# magbead_v4.net
KiCad netlist of a schematic drawn in EAGLE
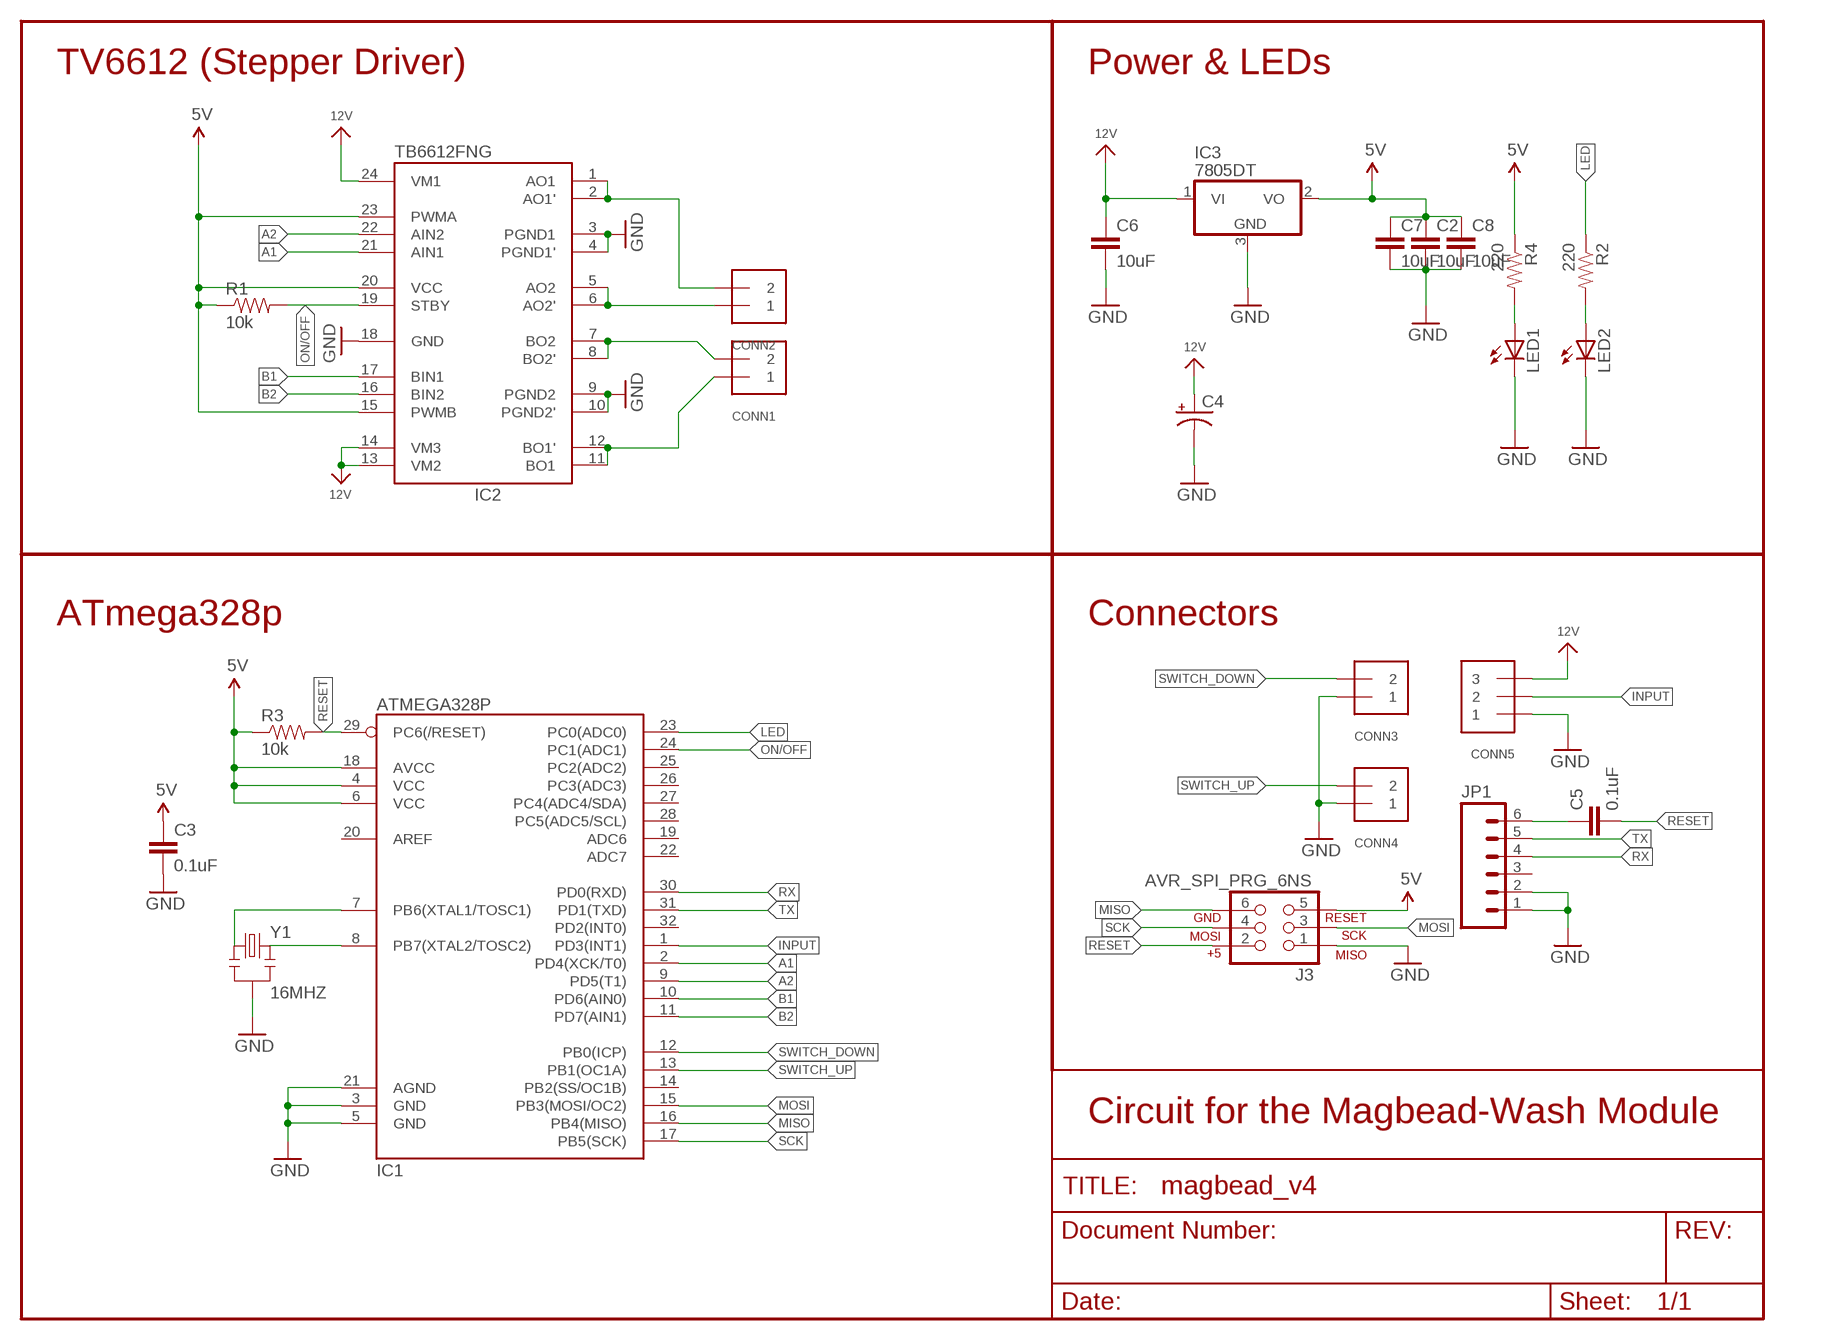
[diagram p0: schematic, sheet 1]

(export (version "E")
  (design (tool "Eeschema 10.0.6"))
  (components
    (comp (ref "C2")
      (value "10uF")
      (footprint "eagle-import:0805")
      (libsource (lib "eagle-import") (part "CAP0805"))
    )
    (comp (ref "C3")
      (value "0.1uF")
      (footprint "eagle-import:0603-CAP")
      (libsource (lib "eagle-import") (part "CAP0603-CAP"))
    )
    (comp (ref "C4")
      (value "CAP_POLD")
      (footprint "eagle-import:PANASONIC_D")
      (libsource (lib "eagle-import") (part "CAP_POLD"))
    )
    (comp (ref "C5")
      (value "0.1uF")
      (footprint "eagle-import:0603-CAP")
      (libsource (lib "eagle-import") (part "CAP0603-CAP"))
    )
    (comp (ref "C6")
      (value "10uF")
      (footprint "eagle-import:0805")
      (libsource (lib "eagle-import") (part "CAP0805"))
    )
    (comp (ref "C7")
      (value "10uF")
      (footprint "eagle-import:0805")
      (libsource (lib "eagle-import") (part "CAP0805"))
    )
    (comp (ref "C8")
      (value "10uF")
      (footprint "eagle-import:0805")
      (libsource (lib "eagle-import") (part "CAP0805"))
    )
    (comp (ref "CONN1")
      (value "TERMBLOCK_1X2")
      (footprint "eagle-import:TERMBLOCK_1X2-3.5MM")
      (libsource (lib "eagle-import") (part "TERMBLOCK_1X2"))
    )
    (comp (ref "CONN2")
      (value "TERMBLOCK_1X2")
      (footprint "eagle-import:TERMBLOCK_1X2-3.5MM")
      (libsource (lib "eagle-import") (part "TERMBLOCK_1X2"))
    )
    (comp (ref "CONN3")
      (value "TERMBLOCK_1X2")
      (footprint "eagle-import:TERMBLOCK_1X2-3.5MM")
      (libsource (lib "eagle-import") (part "TERMBLOCK_1X2"))
    )
    (comp (ref "CONN4")
      (value "TERMBLOCK_1X2")
      (footprint "eagle-import:TERMBLOCK_1X2-3.5MM")
      (libsource (lib "eagle-import") (part "TERMBLOCK_1X2"))
    )
    (comp (ref "CONN5")
      (value "TERMBLOCK_1X3")
      (footprint "eagle-import:TERMBLOCK_1X3-3.5MM")
      (libsource (lib "eagle-import") (part "TERMBLOCK_1X3"))
    )
    (comp (ref "IC1")
      (value "ATMEGA328P")
      (footprint "eagle-import:TQFP32-08")
      (libsource (lib "eagle-import") (part "ATMEGA328_SMT"))
    )
    (comp (ref "IC2")
      (value "TB6612FNG")
      (footprint "eagle-import:SSOP24")
      (libsource (lib "eagle-import") (part "TB6612FNG"))
    )
    (comp (ref "IC3")
      (value "7805DT")
      (footprint "eagle-import:TO252")
      (libsource (lib "eagle-import") (part "78DT05"))
    )
    (comp (ref "J3")
      (value "AVR_SPI_PRG_6NS")
      (footprint "eagle-import:2X3-NS")
      (libsource (lib "eagle-import") (part "AVR_SPI_PRG_6NS"))
    )
    (comp (ref "JP1")
      (value "M06SIP")
      (footprint "eagle-import:1X06")
      (libsource (lib "eagle-import") (part "M06SIP"))
    )
    (comp (ref "LED1")
      (value "LEDCHIP-LED0603")
      (footprint "eagle-import:CHIP-LED0603")
      (libsource (lib "eagle-import") (part "LEDCHIP-LED0603"))
    )
    (comp (ref "LED2")
      (value "LEDCHIP-LED0603")
      (footprint "eagle-import:CHIP-LED0603")
      (libsource (lib "eagle-import") (part "LEDCHIP-LED0603"))
    )
    (comp (ref "R1")
      (value "10k")
      (footprint "eagle-import:0603-RES")
      (libsource (lib "eagle-import") (part "RESISTOR0603-RES"))
    )
    (comp (ref "R2")
      (value "220")
      (footprint "eagle-import:0603-RES")
      (libsource (lib "eagle-import") (part "RESISTOR0603-RES"))
    )
    (comp (ref "R3")
      (value "10k")
      (footprint "eagle-import:0603-RES")
      (libsource (lib "eagle-import") (part "RESISTOR0603-RES"))
    )
    (comp (ref "R4")
      (value "220")
      (footprint "eagle-import:0603-RES")
      (libsource (lib "eagle-import") (part "RESISTOR0603-RES"))
    )
    (comp (ref "Y1")
      (value "16MHZ")
      (footprint "eagle-import:RESONATOR-SMD")
      (libsource (lib "eagle-import") (part "RESONATOR16MHZ"))
    )
  )
  (nets
    (net (code "1") (name "5V") (class "Default")
      (node (ref "C2") (pin "1") (pinfunction "1_1") (pintype "passive"))
      (node (ref "C3") (pin "1") (pinfunction "1_1") (pintype "passive"))
      (node (ref "C7") (pin "1") (pinfunction "1_1") (pintype "passive"))
      (node (ref "C8") (pin "1") (pinfunction "1_1") (pintype "passive"))
      (node (ref "IC1") (pin "18") (pinfunction "AVCC_18") (pintype "bidirectional"))
      (node (ref "IC1") (pin "4") (pinfunction "VCC_4") (pintype "bidirectional"))
      (node (ref "IC1") (pin "6") (pinfunction "VCC_6") (pintype "bidirectional"))
      (node (ref "IC2") (pin "15") (pinfunction "PWMB_15") (pintype "input"))
      (node (ref "IC2") (pin "20") (pinfunction "VCC_20") (pintype "power_in"))
      (node (ref "IC2") (pin "23") (pinfunction "PWMA_23") (pintype "input"))
      (node (ref "IC3") (pin "2") (pinfunction "VO_2") (pintype "passive"))
      (node (ref "J3") (pin "5") (pinfunction "5_5") (pintype "passive"))
      (node (ref "R1") (pin "1") (pinfunction "1_1") (pintype "passive"))
      (node (ref "R3") (pin "1") (pinfunction "1_1") (pintype "passive"))
      (node (ref "R4") (pin "1") (pinfunction "1_1") (pintype "passive"))
    )
    (net (code "2") (name "12V") (class "Default")
      (node (ref "C4") (pin "+") (pinfunction "+_+") (pintype "passive"))
      (node (ref "C6") (pin "1") (pinfunction "1_1") (pintype "passive"))
      (node (ref "CONN5") (pin "3") (pinfunction "3_3") (pintype "passive"))
      (node (ref "IC2") (pin "13") (pinfunction "VM2_13") (pintype "power_in"))
      (node (ref "IC2") (pin "14") (pinfunction "VM3_14") (pintype "power_in"))
      (node (ref "IC2") (pin "24") (pinfunction "VM1_24") (pintype "power_in"))
      (node (ref "IC3") (pin "1") (pinfunction "VI_1") (pintype "input"))
    )
    (net (code "3") (name "A1") (class "Default")
      (node (ref "IC1") (pin "2") (pinfunction "PD4(XCK/T0)_2") (pintype "bidirectional"))
      (node (ref "IC2") (pin "21") (pinfunction "AIN1_21") (pintype "input"))
    )
    (net (code "4") (name "A2") (class "Default")
      (node (ref "IC1") (pin "9") (pinfunction "PD5(T1)_9") (pintype "bidirectional"))
      (node (ref "IC2") (pin "22") (pinfunction "AIN2_22") (pintype "input"))
    )
    (net (code "5") (name "B1") (class "Default")
      (node (ref "IC1") (pin "10") (pinfunction "PD6(AIN0)_10") (pintype "bidirectional"))
      (node (ref "IC2") (pin "17") (pinfunction "BIN1_17") (pintype "input"))
    )
    (net (code "6") (name "B2") (class "Default")
      (node (ref "IC1") (pin "11") (pinfunction "PD7(AIN1)_11") (pintype "bidirectional"))
      (node (ref "IC2") (pin "16") (pinfunction "BIN2_16") (pintype "input"))
    )
    (net (code "7") (name "GND") (class "Default")
      (node (ref "C2") (pin "2") (pinfunction "2_2") (pintype "passive"))
      (node (ref "C3") (pin "2") (pinfunction "2_2") (pintype "passive"))
      (node (ref "C4") (pin "-") (pinfunction "-_-") (pintype "passive"))
      (node (ref "C6") (pin "2") (pinfunction "2_2") (pintype "passive"))
      (node (ref "C7") (pin "2") (pinfunction "2_2") (pintype "passive"))
      (node (ref "C8") (pin "2") (pinfunction "2_2") (pintype "passive"))
      (node (ref "CONN3") (pin "1") (pinfunction "1_1") (pintype "passive"))
      (node (ref "CONN4") (pin "1") (pinfunction "1_1") (pintype "passive"))
      (node (ref "CONN5") (pin "1") (pinfunction "1_1") (pintype "passive"))
      (node (ref "IC1") (pin "21") (pinfunction "AGND_21") (pintype "bidirectional"))
      (node (ref "IC1") (pin "3") (pinfunction "GND_3") (pintype "bidirectional"))
      (node (ref "IC1") (pin "5") (pinfunction "GND_5") (pintype "bidirectional"))
      (node (ref "IC2") (pin "10") (pinfunction "PGND2'_10") (pintype "power_in"))
      (node (ref "IC2") (pin "18") (pinfunction "GND_18") (pintype "power_in"))
      (node (ref "IC2") (pin "3") (pinfunction "PGND1_3") (pintype "power_in"))
      (node (ref "IC2") (pin "4") (pinfunction "PGND1'_4") (pintype "power_in"))
      (node (ref "IC2") (pin "9") (pinfunction "PGND2_9") (pintype "power_in"))
      (node (ref "IC3") (pin "3") (pinfunction "GND_3") (pintype "passive"))
      (node (ref "J3") (pin "1") (pinfunction "1_1") (pintype "passive"))
      (node (ref "JP1") (pin "1") (pinfunction "1_1") (pintype "passive"))
      (node (ref "JP1") (pin "2") (pinfunction "2_2") (pintype "passive"))
      (node (ref "LED1") (pin "C") (pinfunction "C_C") (pintype "passive"))
      (node (ref "LED2") (pin "C") (pinfunction "C_C") (pintype "passive"))
      (node (ref "Y1") (pin "2") (pinfunction "2_2") (pintype "passive"))
    )
    (net (code "8") (name "INPUT") (class "Default")
      (node (ref "CONN5") (pin "2") (pinfunction "2_2") (pintype "passive"))
      (node (ref "IC1") (pin "1") (pinfunction "PD3(INT1)_1") (pintype "bidirectional"))
    )
    (net (code "9") (name "LED") (class "Default")
      (node (ref "IC1") (pin "23") (pinfunction "PC0(ADC0)_23") (pintype "bidirectional"))
      (node (ref "R2") (pin "1") (pinfunction "1_1") (pintype "passive"))
    )
    (net (code "10") (name "MISO") (class "Default")
      (node (ref "IC1") (pin "16") (pinfunction "PB4(MISO)_16") (pintype "bidirectional"))
      (node (ref "J3") (pin "6") (pinfunction "6_6") (pintype "passive"))
    )
    (net (code "11") (name "MOSI") (class "Default")
      (node (ref "IC1") (pin "15") (pinfunction "PB3(MOSI/OC2)_15") (pintype "bidirectional"))
      (node (ref "J3") (pin "3") (pinfunction "3_3") (pintype "passive"))
    )
    (net (code "12") (name "Net-(C5-Pad1)") (class "Default")
      (node (ref "C5") (pin "1") (pinfunction "1_1") (pintype "passive"))
      (node (ref "JP1") (pin "6") (pinfunction "6_6") (pintype "passive"))
    )
    (net (code "13") (name "Net-(IC1-PB6(XTAL1{slash}TOSC1))") (class "Default")
      (node (ref "IC1") (pin "7") (pinfunction "PB6(XTAL1/TOSC1)_7") (pintype "bidirectional"))
      (node (ref "Y1") (pin "1") (pinfunction "1_1") (pintype "passive"))
    )
    (net (code "14") (name "Net-(IC1-PB7(XTAL2{slash}TOSC2))") (class "Default")
      (node (ref "IC1") (pin "8") (pinfunction "PB7(XTAL2/TOSC2)_8") (pintype "bidirectional"))
      (node (ref "Y1") (pin "3") (pinfunction "3_3") (pintype "passive"))
    )
    (net (code "15") (name "Net-(IC2-AO1')") (class "Default")
      (node (ref "CONN2") (pin "2") (pinfunction "2_2") (pintype "passive"))
      (node (ref "IC2") (pin "1") (pinfunction "AO1_1") (pintype "output"))
      (node (ref "IC2") (pin "2") (pinfunction "AO1'_2") (pintype "output"))
    )
    (net (code "16") (name "Net-(IC2-AO2')") (class "Default")
      (node (ref "CONN2") (pin "1") (pinfunction "1_1") (pintype "passive"))
      (node (ref "IC2") (pin "5") (pinfunction "AO2_5") (pintype "output"))
      (node (ref "IC2") (pin "6") (pinfunction "AO2'_6") (pintype "output"))
    )
    (net (code "17") (name "Net-(IC2-BO1')") (class "Default")
      (node (ref "CONN1") (pin "1") (pinfunction "1_1") (pintype "passive"))
      (node (ref "IC2") (pin "11") (pinfunction "BO1_11") (pintype "output"))
      (node (ref "IC2") (pin "12") (pinfunction "BO1'_12") (pintype "output"))
    )
    (net (code "18") (name "Net-(IC2-BO2')") (class "Default")
      (node (ref "CONN1") (pin "2") (pinfunction "2_2") (pintype "passive"))
      (node (ref "IC2") (pin "7") (pinfunction "BO2_7") (pintype "output"))
      (node (ref "IC2") (pin "8") (pinfunction "BO2'_8") (pintype "output"))
    )
    (net (code "19") (name "Net-(LED1-PadA)") (class "Default")
      (node (ref "LED1") (pin "A") (pinfunction "A_A") (pintype "passive"))
      (node (ref "R4") (pin "2") (pinfunction "2_2") (pintype "passive"))
    )
    (net (code "20") (name "Net-(LED2-PadA)") (class "Default")
      (node (ref "LED2") (pin "A") (pinfunction "A_A") (pintype "passive"))
      (node (ref "R2") (pin "2") (pinfunction "2_2") (pintype "passive"))
    )
    (net (code "21") (name "ON{slash}OFF") (class "Default")
      (node (ref "IC1") (pin "24") (pinfunction "PC1(ADC1)_24") (pintype "bidirectional"))
      (node (ref "IC2") (pin "19") (pinfunction "STBY_19") (pintype "input"))
      (node (ref "R1") (pin "2") (pinfunction "2_2") (pintype "passive"))
    )
    (net (code "22") (name "RESET") (class "Default")
      (node (ref "C5") (pin "2") (pinfunction "2_2") (pintype "passive"))
      (node (ref "IC1") (pin "29") (pinfunction "PC6(/RESET)_29") (pintype "bidirectional"))
      (node (ref "J3") (pin "2") (pinfunction "2_2") (pintype "passive"))
      (node (ref "R3") (pin "2") (pinfunction "2_2") (pintype "passive"))
    )
    (net (code "23") (name "RX") (class "Default")
      (node (ref "IC1") (pin "30") (pinfunction "PD0(RXD)_30") (pintype "bidirectional"))
      (node (ref "JP1") (pin "4") (pinfunction "4_4") (pintype "passive"))
    )
    (net (code "24") (name "SCK") (class "Default")
      (node (ref "IC1") (pin "17") (pinfunction "PB5(SCK)_17") (pintype "bidirectional"))
      (node (ref "J3") (pin "4") (pinfunction "4_4") (pintype "passive"))
    )
    (net (code "25") (name "SWITCH_DOWN") (class "Default")
      (node (ref "CONN3") (pin "2") (pinfunction "2_2") (pintype "passive"))
      (node (ref "IC1") (pin "12") (pinfunction "PB0(ICP)_12") (pintype "bidirectional"))
    )
    (net (code "26") (name "SWITCH_UP") (class "Default")
      (node (ref "CONN4") (pin "2") (pinfunction "2_2") (pintype "passive"))
      (node (ref "IC1") (pin "13") (pinfunction "PB1(OC1A)_13") (pintype "bidirectional"))
    )
    (net (code "27") (name "TX") (class "Default")
      (node (ref "IC1") (pin "31") (pinfunction "PD1(TXD)_31") (pintype "bidirectional"))
      (node (ref "JP1") (pin "5") (pinfunction "5_5") (pintype "passive"))
    )
    (net (code "28") (name "unconnected-(IC1-ADC6-Pad19)") (class "Default")
      (node (ref "IC1") (pin "19") (pinfunction "ADC6_19") (pintype "bidirectional"))
    )
    (net (code "29") (name "unconnected-(IC1-ADC7-Pad22)") (class "Default")
      (node (ref "IC1") (pin "22") (pinfunction "ADC7_22") (pintype "bidirectional"))
    )
    (net (code "30") (name "unconnected-(IC1-AREF-Pad20)") (class "Default")
      (node (ref "IC1") (pin "20") (pinfunction "AREF_20") (pintype "bidirectional"))
    )
    (net (code "31") (name "unconnected-(IC1-PB2(SS{slash}OC1B)-Pad14)") (class "Default")
      (node (ref "IC1") (pin "14") (pinfunction "PB2(SS/OC1B)_14") (pintype "bidirectional"))
    )
    (net (code "32") (name "unconnected-(IC1-PC2(ADC2)-Pad25)") (class "Default")
      (node (ref "IC1") (pin "25") (pinfunction "PC2(ADC2)_25") (pintype "bidirectional"))
    )
    (net (code "33") (name "unconnected-(IC1-PC3(ADC3)-Pad26)") (class "Default")
      (node (ref "IC1") (pin "26") (pinfunction "PC3(ADC3)_26") (pintype "bidirectional"))
    )
    (net (code "34") (name "unconnected-(IC1-PC4(ADC4{slash}SDA)-Pad27)") (class "Default")
      (node (ref "IC1") (pin "27") (pinfunction "PC4(ADC4/SDA)_27") (pintype "bidirectional"))
    )
    (net (code "35") (name "unconnected-(IC1-PC5(ADC5{slash}SCL)-Pad28)") (class "Default")
      (node (ref "IC1") (pin "28") (pinfunction "PC5(ADC5/SCL)_28") (pintype "bidirectional"))
    )
    (net (code "36") (name "unconnected-(IC1-PD2(INT0)-Pad32)") (class "Default")
      (node (ref "IC1") (pin "32") (pinfunction "PD2(INT0)_32") (pintype "bidirectional"))
    )
    (net (code "37") (name "unconnected-(JP1-Pad3)") (class "Default")
      (node (ref "JP1") (pin "3") (pinfunction "3_3") (pintype "passive"))
    )
  )
)
